# Relay_30A__sla_12v_slc_v1_0.net
KiCad netlist of a schematic drawn in EAGLE
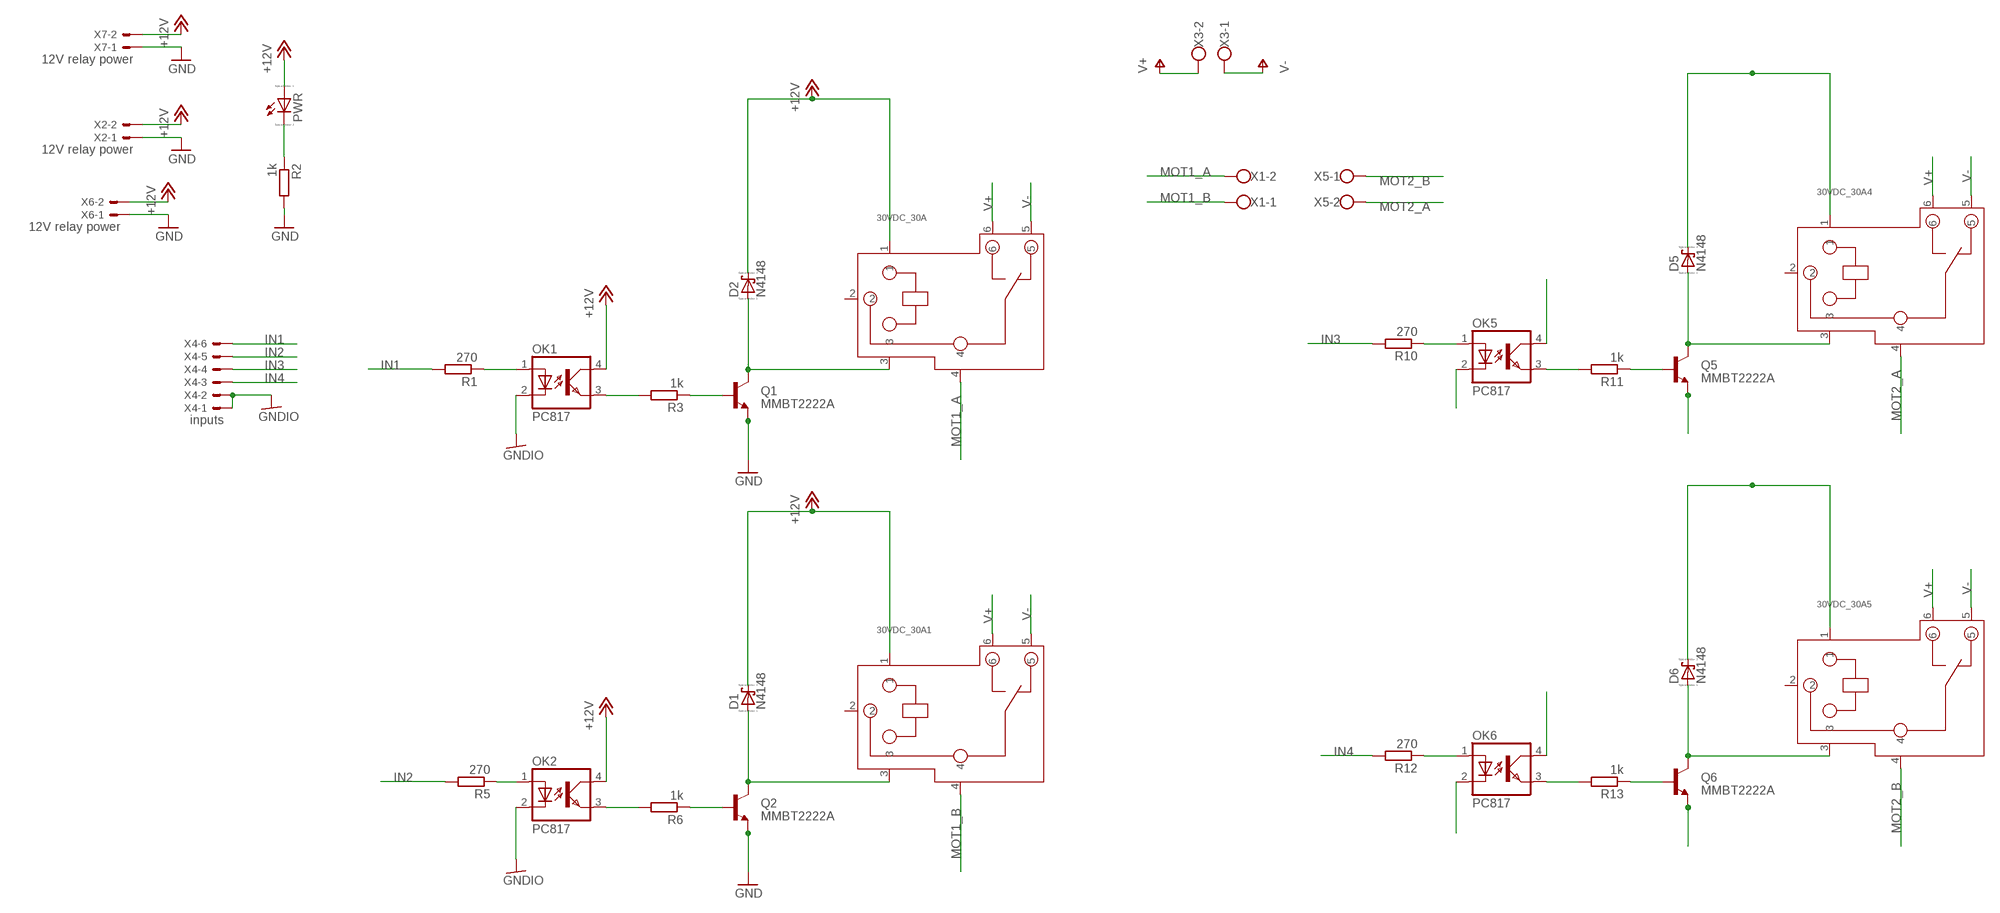
[diagram p0: schematic, sheet 1]

(export (version "E")
  (design (tool "Eeschema 10.0.6"))
  (components
    (comp (ref "30VDC_30A")
      (value "RELAY-SLA-05VDC-SL-C")
      (footprint "eagle-import:6P-19.8H")
      (libsource (lib "eagle-import") (part "RELAY-SLA-05VDC-SL-C"))
    )
    (comp (ref "30VDC_30A1")
      (value "RELAY-SLA-05VDC-SL-C")
      (footprint "eagle-import:6P-19.8H")
      (libsource (lib "eagle-import") (part "RELAY-SLA-05VDC-SL-C"))
    )
    (comp (ref "30VDC_30A4")
      (value "RELAY-SLA-05VDC-SL-C")
      (footprint "eagle-import:6P-19.8H")
      (libsource (lib "eagle-import") (part "RELAY-SLA-05VDC-SL-C"))
    )
    (comp (ref "30VDC_30A5")
      (value "RELAY-SLA-05VDC-SL-C")
      (footprint "eagle-import:6P-19.8H")
      (libsource (lib "eagle-import") (part "RELAY-SLA-05VDC-SL-C"))
    )
    (comp (ref "D1")
      (value "N4148")
      (footprint "eagle-import:DIODE_F126Z12")
      (libsource (lib "eagle-import") (part "SCHOTTKY-DIODEF126Z12"))
    )
    (comp (ref "D2")
      (value "N4148")
      (footprint "eagle-import:DIODE_F126Z12")
      (libsource (lib "eagle-import") (part "SCHOTTKY-DIODEF126Z12"))
    )
    (comp (ref "D5")
      (value "N4148")
      (footprint "eagle-import:DIODE_F126Z12")
      (libsource (lib "eagle-import") (part "SCHOTTKY-DIODEF126Z12"))
    )
    (comp (ref "D6")
      (value "N4148")
      (footprint "eagle-import:DIODE_F126Z12")
      (libsource (lib "eagle-import") (part "SCHOTTKY-DIODEF126Z12"))
    )
    (comp (ref "OK1")
      (value "PC817")
      (footprint "eagle-import:DIL04")
      (fields (field (name "MPN") "PC817X4J000F"))
      (libsource (lib "eagle-import") (part "PC817"))
    )
    (comp (ref "OK2")
      (value "PC817")
      (footprint "eagle-import:DIL04")
      (fields (field (name "MPN") "PC817X4J000F"))
      (libsource (lib "eagle-import") (part "PC817"))
    )
    (comp (ref "OK5")
      (value "PC817")
      (footprint "eagle-import:DIL04")
      (fields (field (name "MPN") "PC817X4J000F"))
      (libsource (lib "eagle-import") (part "PC817"))
    )
    (comp (ref "OK6")
      (value "PC817")
      (footprint "eagle-import:DIL04")
      (fields (field (name "MPN") "PC817X4J000F"))
      (libsource (lib "eagle-import") (part "PC817"))
    )
    (comp (ref "PWR")
      (value "LED_ELD260")
      (footprint "eagle-import:LED_LD260")
      (libsource (lib "eagle-import") (part "LED_ELD260"))
    )
    (comp (ref "Q1")
      (value "MMBT2222A")
      (footprint "eagle-import:TO-92")
      (libsource (lib "eagle-import") (part "TRANSISTOR_NPNTO92"))
    )
    (comp (ref "Q2")
      (value "MMBT2222A")
      (footprint "eagle-import:TO-92")
      (libsource (lib "eagle-import") (part "TRANSISTOR_NPNTO92"))
    )
    (comp (ref "Q5")
      (value "MMBT2222A")
      (footprint "eagle-import:TO-92")
      (libsource (lib "eagle-import") (part "TRANSISTOR_NPNTO92"))
    )
    (comp (ref "Q6")
      (value "MMBT2222A")
      (footprint "eagle-import:TO-92")
      (libsource (lib "eagle-import") (part "TRANSISTOR_NPNTO92"))
    )
    (comp (ref "R1")
      (value "270")
      (footprint "eagle-import:0204_7")
      (libsource (lib "eagle-import") (part "R-EU_0204/7"))
    )
    (comp (ref "R2")
      (value "1k")
      (footprint "eagle-import:0204_5")
      (libsource (lib "eagle-import") (part "R-EU_0204/5"))
    )
    (comp (ref "R3")
      (value "1k")
      (footprint "eagle-import:0204_7")
      (libsource (lib "eagle-import") (part "R-EU_0204/7"))
    )
    (comp (ref "R5")
      (value "270")
      (footprint "eagle-import:0204_5")
      (libsource (lib "eagle-import") (part "R-EU_0204/5"))
    )
    (comp (ref "R6")
      (value "1k")
      (footprint "eagle-import:0204_7")
      (libsource (lib "eagle-import") (part "R-EU_0204/7"))
    )
    (comp (ref "R10")
      (value "270")
      (footprint "eagle-import:0207_10")
      (libsource (lib "eagle-import") (part "R-EU_0207/10"))
    )
    (comp (ref "R11")
      (value "1k")
      (footprint "eagle-import:0204_7")
      (libsource (lib "eagle-import") (part "R-EU_0204/7"))
    )
    (comp (ref "R12")
      (value "270")
      (footprint "eagle-import:0204_5")
      (libsource (lib "eagle-import") (part "R-EU_0204/5"))
    )
    (comp (ref "R13")
      (value "1k")
      (footprint "eagle-import:0204_7")
      (libsource (lib "eagle-import") (part "R-EU_0204/7"))
    )
    (comp (ref "X1")
      (value "W237-102")
      (footprint "eagle-import:W237-102")
      (fields (field (name "MPN") "237-102"))
      (libsource (lib "eagle-import") (part "W237-102"))
    )
    (comp (ref "X2")
      (value "12V relay power")
      (footprint "eagle-import:JST-XH-02-PACKAGE-LONG-PAD")
      (libsource (lib "eagle-import") (part "JST-XH-02-PIN-LONG-PAD"))
    )
    (comp (ref "X3")
      (value "W237-102")
      (footprint "eagle-import:W237-102")
      (fields (field (name "MPN") "237-102"))
      (libsource (lib "eagle-import") (part "W237-102"))
    )
    (comp (ref "X4")
      (value "inputs")
      (footprint "eagle-import:JST-XH-06-PACKAGE-LONG-PAD")
      (libsource (lib "eagle-import") (part "JST-XH-06-PIN-LONG-PAD"))
    )
    (comp (ref "X5")
      (value "W237-102")
      (footprint "eagle-import:W237-102")
      (fields (field (name "MPN") "237-102"))
      (libsource (lib "eagle-import") (part "W237-102"))
    )
    (comp (ref "X6")
      (value "12V relay power")
      (footprint "eagle-import:JST-XH-02-PACKAGE-LONG-PAD")
      (libsource (lib "eagle-import") (part "JST-XH-02-PIN-LONG-PAD"))
    )
    (comp (ref "X7")
      (value "12V relay power")
      (footprint "eagle-import:JST-XH-02-PACKAGE-LONG-PAD")
      (libsource (lib "eagle-import") (part "JST-XH-02-PIN-LONG-PAD"))
    )
  )
  (nets
    (net (code "1") (name "+12V") (class "Default")
      (node (ref "30VDC_30A") (pin "1") (pinfunction "1_1") (pintype "bidirectional"))
      (node (ref "30VDC_30A1") (pin "1") (pinfunction "1_1") (pintype "bidirectional"))
      (node (ref "30VDC_30A4") (pin "1") (pinfunction "1_1") (pintype "bidirectional"))
      (node (ref "30VDC_30A5") (pin "1") (pinfunction "1_1") (pintype "bidirectional"))
      (node (ref "D1") (pin "C") (pinfunction "A_C") (pintype "passive"))
      (node (ref "D2") (pin "C") (pinfunction "A_C") (pintype "passive"))
      (node (ref "D5") (pin "C") (pinfunction "A_C") (pintype "passive"))
      (node (ref "D6") (pin "C") (pinfunction "A_C") (pintype "passive"))
      (node (ref "OK1") (pin "4") (pinfunction "COL_4") (pintype "passive"))
      (node (ref "OK2") (pin "4") (pinfunction "COL_4") (pintype "passive"))
      (node (ref "OK5") (pin "4") (pinfunction "COL_4") (pintype "passive"))
      (node (ref "OK6") (pin "4") (pinfunction "COL_4") (pintype "passive"))
      (node (ref "PWR") (pin "A") (pinfunction "A_A") (pintype "passive"))
      (node (ref "X2") (pin "2") (pinfunction "S_2") (pintype "passive"))
      (node (ref "X6") (pin "2") (pinfunction "S_2") (pintype "passive"))
      (node (ref "X7") (pin "2") (pinfunction "S_2") (pintype "passive"))
    )
    (net (code "2") (name "/IN1") (class "Default")
      (node (ref "R1") (pin "2") (pinfunction "2_2") (pintype "passive"))
      (node (ref "X4") (pin "6") (pinfunction "S_6") (pintype "passive"))
    )
    (net (code "3") (name "/IN2") (class "Default")
      (node (ref "R5") (pin "2") (pinfunction "2_2") (pintype "passive"))
      (node (ref "X4") (pin "5") (pinfunction "S_5") (pintype "passive"))
    )
    (net (code "4") (name "/IN3") (class "Default")
      (node (ref "R10") (pin "2") (pinfunction "2_2") (pintype "passive"))
      (node (ref "X4") (pin "4") (pinfunction "S_4") (pintype "passive"))
    )
    (net (code "5") (name "/IN4") (class "Default")
      (node (ref "R12") (pin "2") (pinfunction "2_2") (pintype "passive"))
      (node (ref "X4") (pin "3") (pinfunction "S_3") (pintype "passive"))
    )
    (net (code "6") (name "/MOT1_A") (class "Default")
      (node (ref "30VDC_30A") (pin "4") (pinfunction "4_4") (pintype "bidirectional"))
      (node (ref "X1") (pin "2") (pinfunction "KL_2") (pintype "passive"))
    )
    (net (code "7") (name "/MOT1_B") (class "Default")
      (node (ref "30VDC_30A1") (pin "4") (pinfunction "4_4") (pintype "bidirectional"))
      (node (ref "X1") (pin "1") (pinfunction "KL_1") (pintype "passive"))
    )
    (net (code "8") (name "/MOT2_A") (class "Default")
      (node (ref "30VDC_30A4") (pin "4") (pinfunction "4_4") (pintype "bidirectional"))
      (node (ref "X5") (pin "2") (pinfunction "KL_2") (pintype "passive"))
    )
    (net (code "9") (name "/MOT2_B") (class "Default")
      (node (ref "30VDC_30A5") (pin "4") (pinfunction "4_4") (pintype "bidirectional"))
      (node (ref "X5") (pin "1") (pinfunction "KL_1") (pintype "passive"))
    )
    (net (code "10") (name "GND") (class "Default")
      (node (ref "Q1") (pin "1") (pinfunction "E_1") (pintype "passive"))
      (node (ref "Q2") (pin "1") (pinfunction "E_1") (pintype "passive"))
      (node (ref "Q5") (pin "1") (pinfunction "E_1") (pintype "passive"))
      (node (ref "Q6") (pin "1") (pinfunction "E_1") (pintype "passive"))
      (node (ref "R2") (pin "2") (pinfunction "2_2") (pintype "passive"))
      (node (ref "X2") (pin "1") (pinfunction "S_1") (pintype "passive"))
      (node (ref "X6") (pin "1") (pinfunction "S_1") (pintype "passive"))
      (node (ref "X7") (pin "1") (pinfunction "S_1") (pintype "passive"))
    )
    (net (code "11") (name "GNDIO") (class "Default")
      (node (ref "OK1") (pin "2") (pinfunction "C_2") (pintype "passive"))
      (node (ref "OK2") (pin "2") (pinfunction "C_2") (pintype "passive"))
      (node (ref "OK5") (pin "2") (pinfunction "C_2") (pintype "passive"))
      (node (ref "OK6") (pin "2") (pinfunction "C_2") (pintype "passive"))
      (node (ref "X4") (pin "1") (pinfunction "S_1") (pintype "passive"))
      (node (ref "X4") (pin "2") (pinfunction "S_2") (pintype "passive"))
    )
    (net (code "12") (name "Net-(D1-C)") (class "Default")
      (node (ref "30VDC_30A1") (pin "3") (pinfunction "3_3") (pintype "bidirectional"))
      (node (ref "D1") (pin "A") (pinfunction "C_A") (pintype "passive"))
      (node (ref "Q2") (pin "3") (pinfunction "C_3") (pintype "passive"))
    )
    (net (code "13") (name "Net-(D2-C)") (class "Default")
      (node (ref "30VDC_30A") (pin "3") (pinfunction "3_3") (pintype "bidirectional"))
      (node (ref "D2") (pin "A") (pinfunction "C_A") (pintype "passive"))
      (node (ref "Q1") (pin "3") (pinfunction "C_3") (pintype "passive"))
    )
    (net (code "14") (name "Net-(D5-C)") (class "Default")
      (node (ref "30VDC_30A4") (pin "3") (pinfunction "3_3") (pintype "bidirectional"))
      (node (ref "D5") (pin "A") (pinfunction "C_A") (pintype "passive"))
      (node (ref "Q5") (pin "3") (pinfunction "C_3") (pintype "passive"))
    )
    (net (code "15") (name "Net-(D6-C)") (class "Default")
      (node (ref "30VDC_30A5") (pin "3") (pinfunction "3_3") (pintype "bidirectional"))
      (node (ref "D6") (pin "A") (pinfunction "C_A") (pintype "passive"))
      (node (ref "Q6") (pin "3") (pinfunction "C_3") (pintype "passive"))
    )
    (net (code "16") (name "Net-(OK1-A)") (class "Default")
      (node (ref "OK1") (pin "1") (pinfunction "A_1") (pintype "passive"))
      (node (ref "R1") (pin "1") (pinfunction "1_1") (pintype "passive"))
    )
    (net (code "17") (name "Net-(OK1-EMIT)") (class "Default")
      (node (ref "OK1") (pin "3") (pinfunction "EMIT_3") (pintype "passive"))
      (node (ref "R3") (pin "2") (pinfunction "2_2") (pintype "passive"))
    )
    (net (code "18") (name "Net-(OK2-A)") (class "Default")
      (node (ref "OK2") (pin "1") (pinfunction "A_1") (pintype "passive"))
      (node (ref "R5") (pin "1") (pinfunction "1_1") (pintype "passive"))
    )
    (net (code "19") (name "Net-(OK2-EMIT)") (class "Default")
      (node (ref "OK2") (pin "3") (pinfunction "EMIT_3") (pintype "passive"))
      (node (ref "R6") (pin "2") (pinfunction "2_2") (pintype "passive"))
    )
    (net (code "20") (name "Net-(OK5-A)") (class "Default")
      (node (ref "OK5") (pin "1") (pinfunction "A_1") (pintype "passive"))
      (node (ref "R10") (pin "1") (pinfunction "1_1") (pintype "passive"))
    )
    (net (code "21") (name "Net-(OK5-EMIT)") (class "Default")
      (node (ref "OK5") (pin "3") (pinfunction "EMIT_3") (pintype "passive"))
      (node (ref "R11") (pin "2") (pinfunction "2_2") (pintype "passive"))
    )
    (net (code "22") (name "Net-(OK6-A)") (class "Default")
      (node (ref "OK6") (pin "1") (pinfunction "A_1") (pintype "passive"))
      (node (ref "R12") (pin "1") (pinfunction "1_1") (pintype "passive"))
    )
    (net (code "23") (name "Net-(OK6-EMIT)") (class "Default")
      (node (ref "OK6") (pin "3") (pinfunction "EMIT_3") (pintype "passive"))
      (node (ref "R13") (pin "2") (pinfunction "2_2") (pintype "passive"))
    )
    (net (code "24") (name "Net-(PWR-C)") (class "Default")
      (node (ref "PWR") (pin "K") (pinfunction "C_K") (pintype "passive"))
      (node (ref "R2") (pin "1") (pinfunction "1_1") (pintype "passive"))
    )
    (net (code "25") (name "Net-(Q1-B)") (class "Default")
      (node (ref "Q1") (pin "2") (pinfunction "B_2") (pintype "passive"))
      (node (ref "R3") (pin "1") (pinfunction "1_1") (pintype "passive"))
    )
    (net (code "26") (name "Net-(Q2-B)") (class "Default")
      (node (ref "Q2") (pin "2") (pinfunction "B_2") (pintype "passive"))
      (node (ref "R6") (pin "1") (pinfunction "1_1") (pintype "passive"))
    )
    (net (code "27") (name "Net-(Q5-B)") (class "Default")
      (node (ref "Q5") (pin "2") (pinfunction "B_2") (pintype "passive"))
      (node (ref "R11") (pin "1") (pinfunction "1_1") (pintype "passive"))
    )
    (net (code "28") (name "Net-(Q6-B)") (class "Default")
      (node (ref "Q6") (pin "2") (pinfunction "B_2") (pintype "passive"))
      (node (ref "R13") (pin "1") (pinfunction "1_1") (pintype "passive"))
    )
    (net (code "29") (name "V+") (class "Default")
      (node (ref "30VDC_30A") (pin "6") (pinfunction "6_6") (pintype "bidirectional"))
      (node (ref "30VDC_30A1") (pin "6") (pinfunction "6_6") (pintype "bidirectional"))
      (node (ref "30VDC_30A4") (pin "6") (pinfunction "6_6") (pintype "bidirectional"))
      (node (ref "30VDC_30A5") (pin "6") (pinfunction "6_6") (pintype "bidirectional"))
      (node (ref "X3") (pin "2") (pinfunction "KL_2") (pintype "passive"))
    )
    (net (code "30") (name "V-") (class "Default")
      (node (ref "30VDC_30A") (pin "5") (pinfunction "5_5") (pintype "bidirectional"))
      (node (ref "30VDC_30A1") (pin "5") (pinfunction "5_5") (pintype "bidirectional"))
      (node (ref "30VDC_30A4") (pin "5") (pinfunction "5_5") (pintype "bidirectional"))
      (node (ref "30VDC_30A5") (pin "5") (pinfunction "5_5") (pintype "bidirectional"))
      (node (ref "X3") (pin "1") (pinfunction "KL_1") (pintype "passive"))
    )
    (net (code "31") (name "unconnected-(30VDC_30A-Pad2)") (class "Default")
      (node (ref "30VDC_30A") (pin "2") (pinfunction "2_2") (pintype "bidirectional"))
    )
    (net (code "32") (name "unconnected-(30VDC_30A1-Pad2)") (class "Default")
      (node (ref "30VDC_30A1") (pin "2") (pinfunction "2_2") (pintype "bidirectional"))
    )
    (net (code "33") (name "unconnected-(30VDC_30A4-Pad2)") (class "Default")
      (node (ref "30VDC_30A4") (pin "2") (pinfunction "2_2") (pintype "bidirectional"))
    )
    (net (code "34") (name "unconnected-(30VDC_30A5-Pad2)") (class "Default")
      (node (ref "30VDC_30A5") (pin "2") (pinfunction "2_2") (pintype "bidirectional"))
    )
  )
)
